# schematic-easyeda.net
KiCad netlist of a schematic drawn in EasyEDA
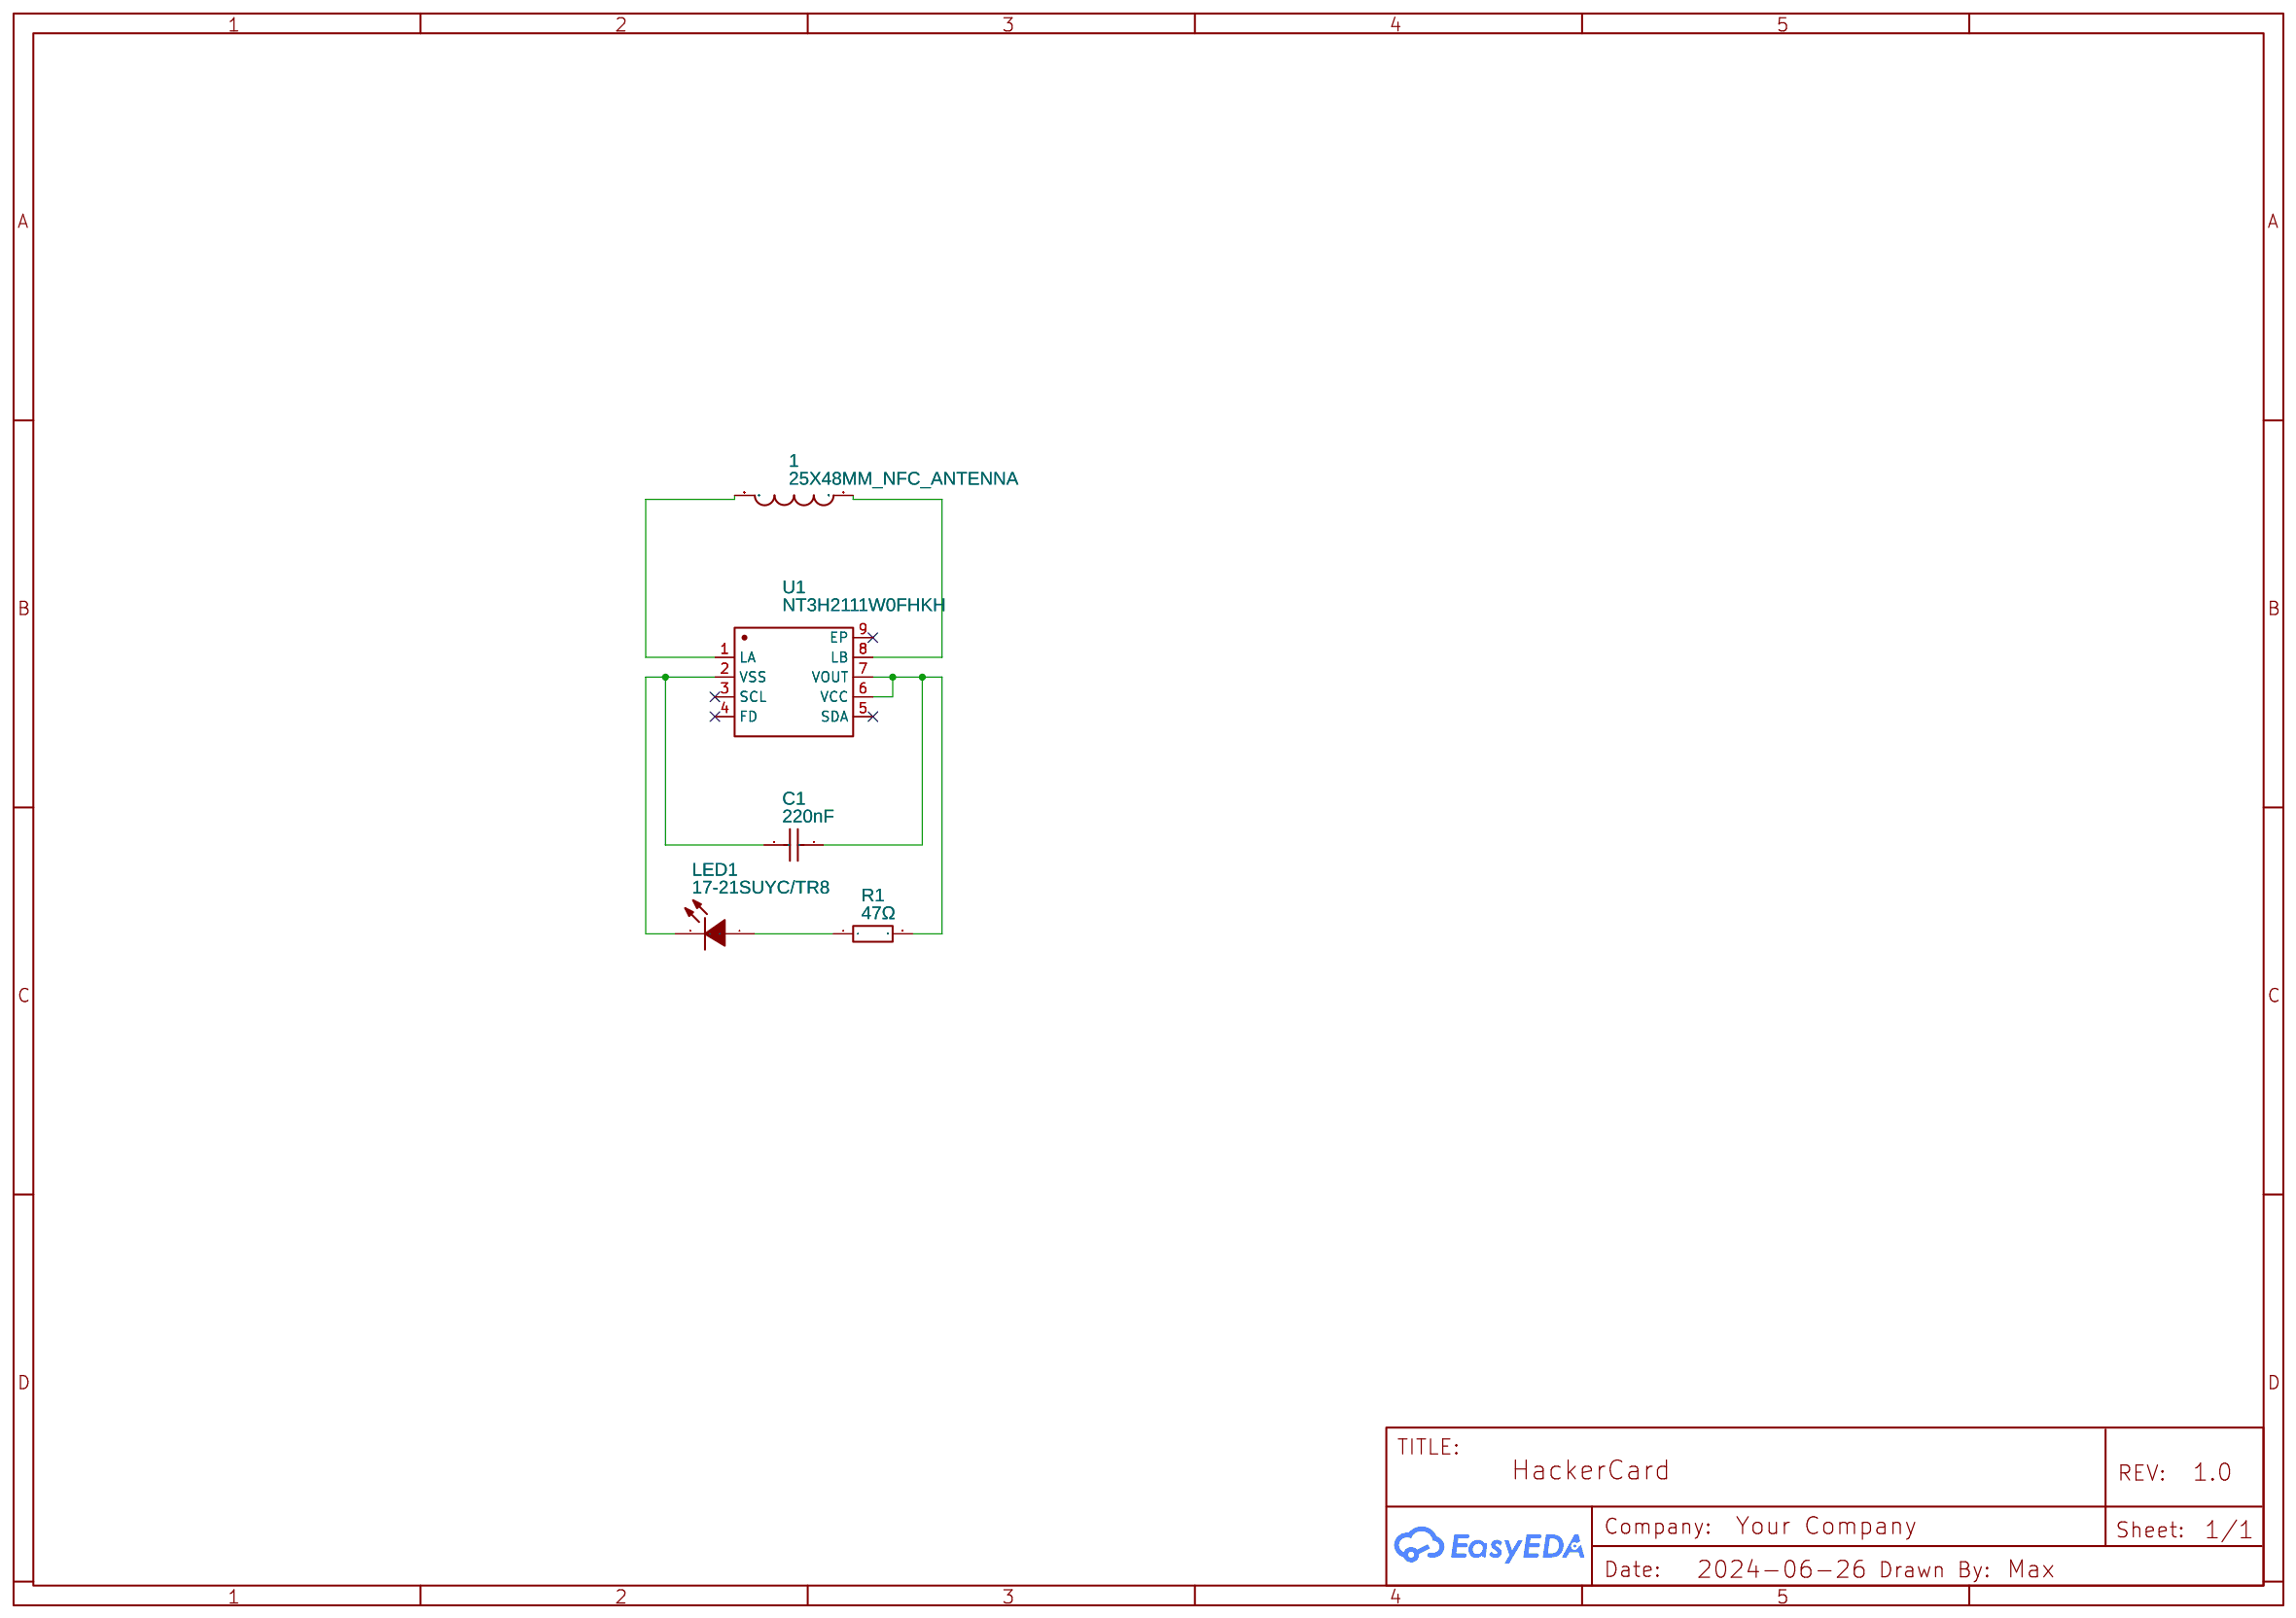
[diagram p0: schematic sheet]

(export (version "E")
  (design (tool "Eeschema 10.0.6"))
  (components
    (comp (ref "1") (value "25X48MM_NFC_ANTENNA") (libsource (lib "") (part "25X48MM_NFC_ANTENNA")))
    (comp (ref "C1")
      (value "220nF")
      (fields
        (field (name "Manufacturer Part") "CL10B224KA8NNNC")
        (field (name "Manufacturer") "SAMSUNG(三星)")
      )
      (libsource (lib "") (part "CL10B224KA8NNNC"))
    )
    (comp (ref "LED1")
      (value "17-21SUYC/TR8")
      (fields (field (name "Manufacturer Part") "KT-0805黄灯") (field (name "Manufacturer") "KENTO"))
      (libsource (lib "") (part "17-21SUYC/TR8"))
    )
    (comp (ref "R1")
      (value "47Ω")
      (fields
        (field (name "Manufacturer Part") "0603WAF470JT5E")
        (field (name "Manufacturer") "UNI-ROYAL(厚声)")
      )
      (libsource (lib "") (part "0603WAF470JT5E"))
    )
    (comp (ref "U1")
      (value "NT3H2111W0FHKH")
      (fields (field (name "Manufacturer") "NXP(恩智浦)"))
      (libsource (lib "") (part "NT3H2111W0FHKH"))
    )
  )
  (nets
    (net (code "1") (name "Net-(LED1-+)") (class "Default")
      (node (ref "LED1") (pin "1") (pinfunction "+_1") (pintype "unspecified"))
      (node (ref "R1") (pin "1") (pinfunction "1_1") (pintype "input"))
    )
    (net (code "2") (name "Net-(LED1--)") (class "Default")
      (node (ref "C1") (pin "1") (pinfunction "1_1") (pintype "input"))
      (node (ref "LED1") (pin "2") (pinfunction "-_2") (pintype "unspecified"))
      (node (ref "U1") (pin "2") (pinfunction "VSS_2") (pintype "unspecified"))
    )
    (net (code "3") (name "Net-(U1-LA)") (class "Default")
      (node (ref "1") (pin "P$2") (pinfunction "P$2_P$2") (pintype "bidirectional"))
      (node (ref "U1") (pin "1") (pinfunction "LA_1") (pintype "unspecified"))
    )
    (net (code "4") (name "Net-(U1-LB)") (class "Default")
      (node (ref "1") (pin "P$1") (pinfunction "P$1_P$1") (pintype "bidirectional"))
      (node (ref "U1") (pin "8") (pinfunction "LB_8") (pintype "unspecified"))
    )
    (net (code "5") (name "Net-(U1-VCC)") (class "Default")
      (node (ref "C1") (pin "2") (pinfunction "2_2") (pintype "input"))
      (node (ref "R1") (pin "2") (pinfunction "2_2") (pintype "input"))
      (node (ref "U1") (pin "6") (pinfunction "VCC_6") (pintype "unspecified"))
      (node (ref "U1") (pin "7") (pinfunction "VOUT_7") (pintype "unspecified"))
    )
    (net (code "6") (name "unconnected-(U1-EP-Pad9)") (class "Default")
      (node (ref "U1") (pin "9") (pinfunction "EP_9") (pintype "unspecified+no_connect"))
    )
    (net (code "7") (name "unconnected-(U1-FD-Pad4)") (class "Default")
      (node (ref "U1") (pin "4") (pinfunction "FD_4") (pintype "unspecified+no_connect"))
    )
    (net (code "8") (name "unconnected-(U1-SCL-Pad3)") (class "Default")
      (node (ref "U1") (pin "3") (pinfunction "SCL_3") (pintype "unspecified+no_connect"))
    )
    (net (code "9") (name "unconnected-(U1-SDA-Pad5)") (class "Default")
      (node (ref "U1") (pin "5") (pinfunction "SDA_5") (pintype "unspecified+no_connect"))
    )
  )
)
